# FE_Channel.net
KiCad netlist of a schematic drawn in Altium Designer
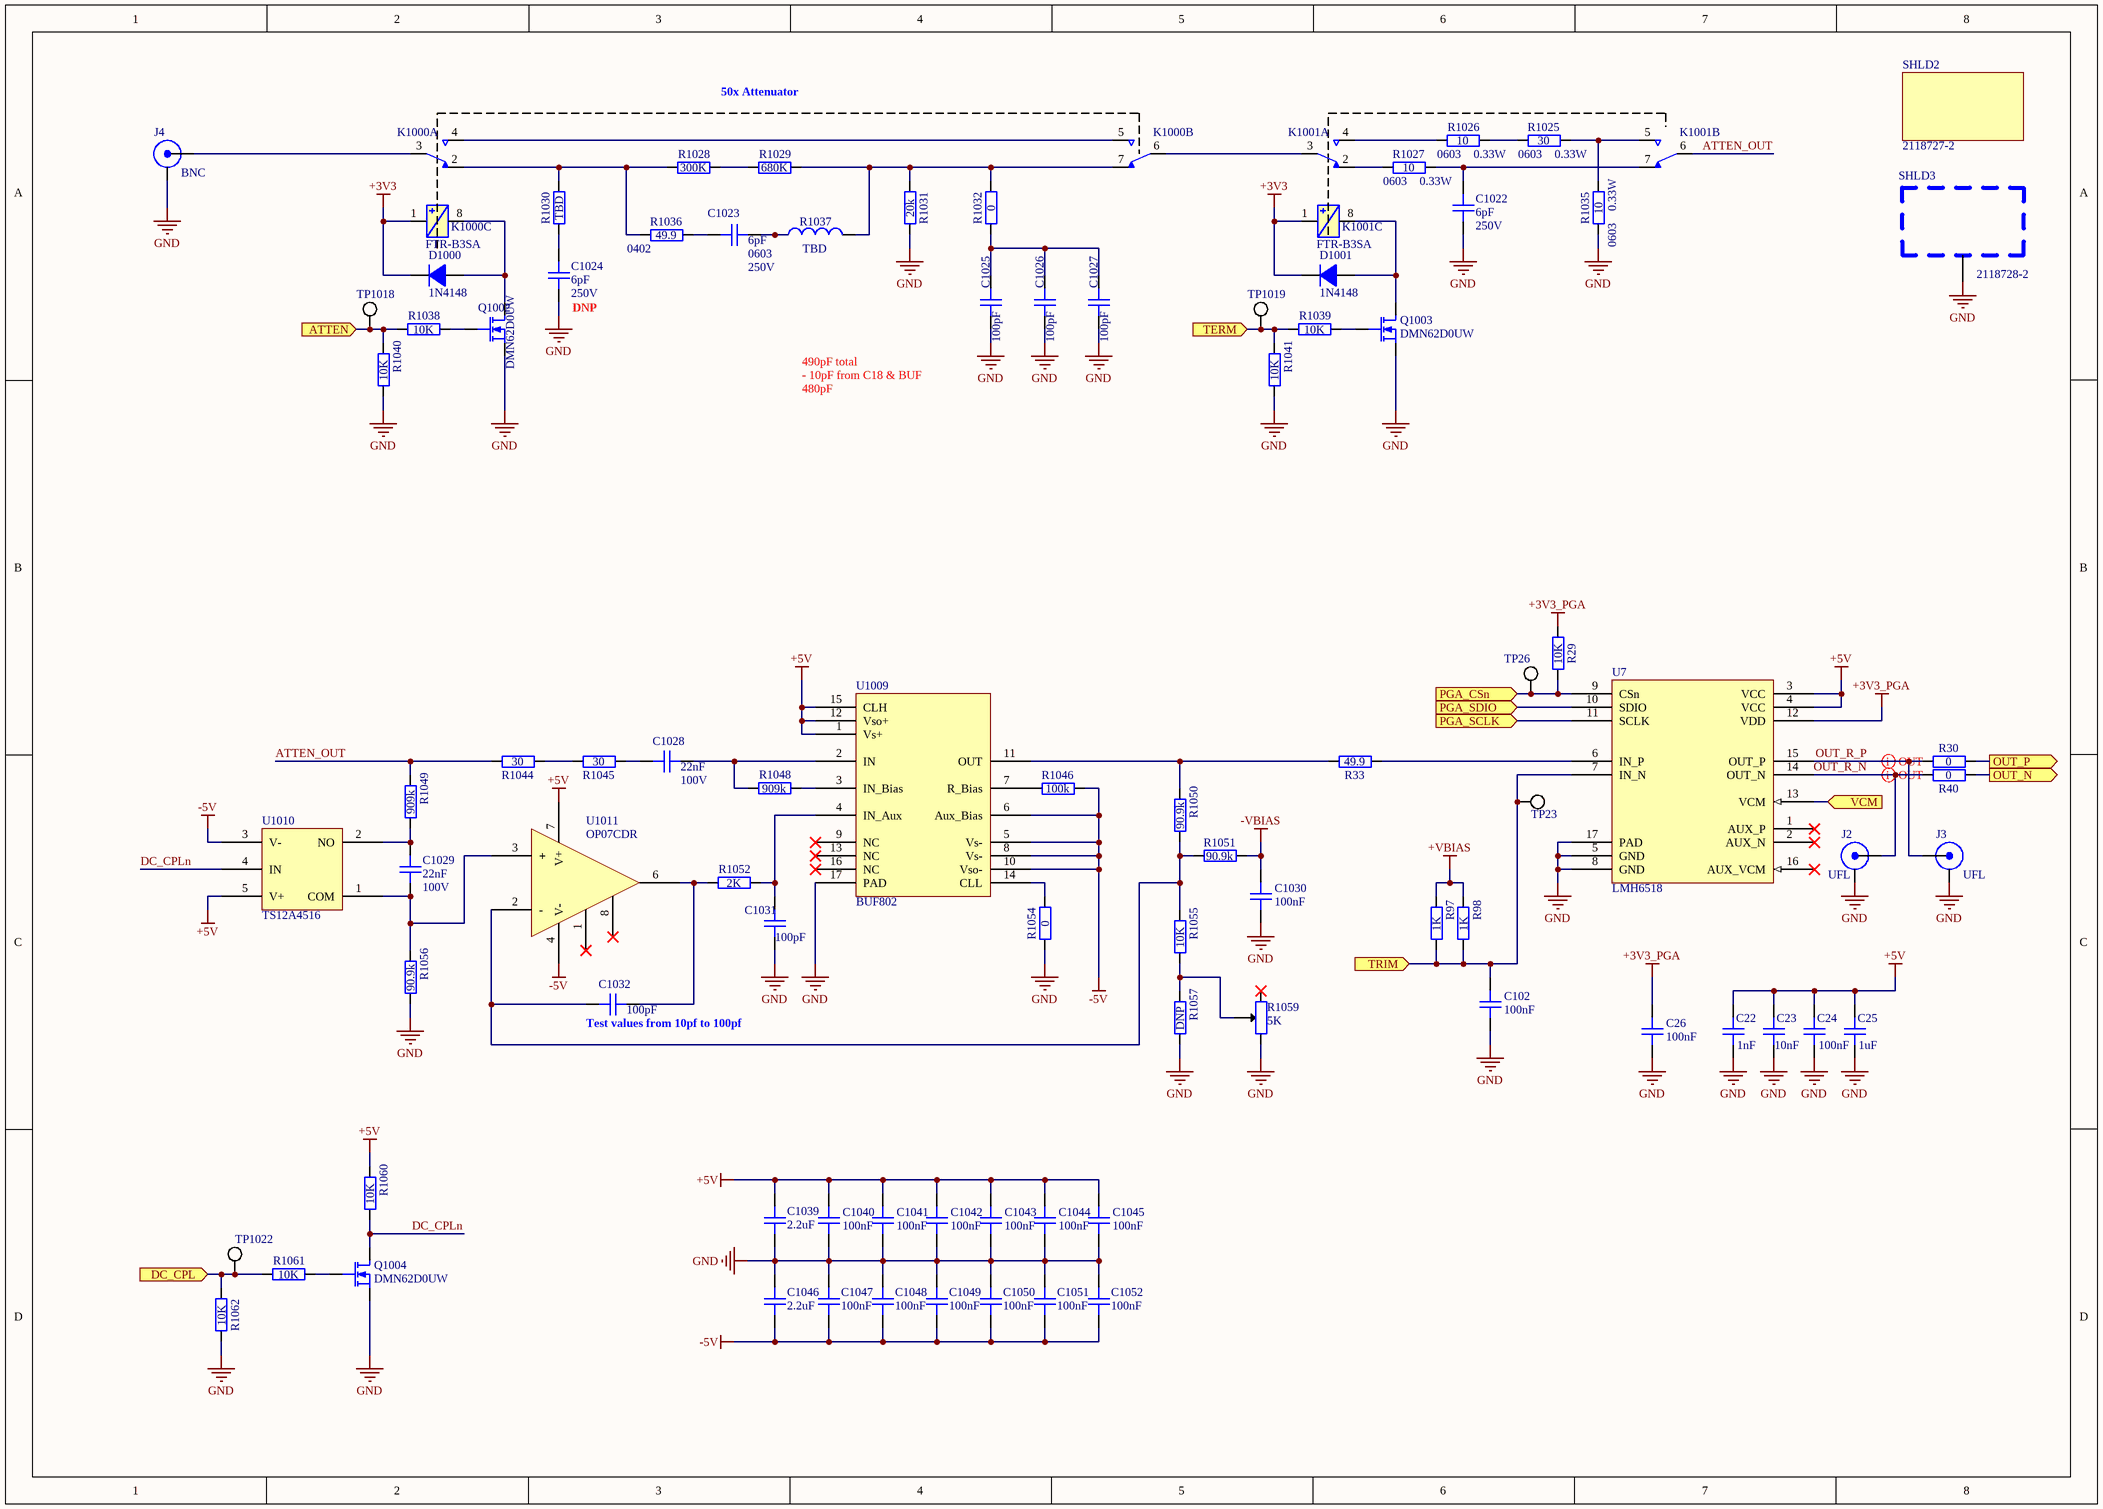
[diagram p0: FE_Channel.SchDoc]

(export (version "E")
  (design (tool "Eeschema 10.0.6"))
  (components
    (comp (ref "C22")
      (value "1nF")
      (footprint "GEN_C_0402")
      (libsource (lib "DSO") (part "CAP 1nF 50V C0G 0402"))
    )
    (comp (ref "C23")
      (value "10nF")
      (footprint "GEN_C_0402")
      (libsource (lib "DSO") (part "CAP 10nF 50V X7R 0402"))
    )
    (comp (ref "C24")
      (value "100nF")
      (footprint "GEN_C_0402")
      (libsource (lib "DSO") (part "CAP 100nF 16V X7R 0402"))
    )
    (comp (ref "C25")
      (value "1uF")
      (footprint "GEN_C_0402")
      (libsource (lib "DSO") (part "CAP 1uF 25V X5R 0402"))
    )
    (comp (ref "C26")
      (value "100nF")
      (footprint "GEN_C_0402")
      (libsource (lib "DSO") (part "CAP 100nF 16V X7R 0402"))
    )
    (comp (ref "C102")
      (value "100nF")
      (footprint "GEN_C_0402")
      (libsource (lib "DSO") (part "CAP 100nF 16V X7R 0402"))
    )
    (comp (ref "C1022")
      (value "6pF")
      (footprint "GEN_C_0603")
      (fields
        (field (name "MANUFACTURER") "KEMET")
        (field (name "MANUFACTURER PART NUMBER") "CBR06C609BAGAC")
        (field (name "VOLTAGE RATING") "250V")
      )
      (libsource (lib "DSO") (part "CAP 6pF 250V C0G 0603"))
    )
    (comp (ref "C1023")
      (value "6pF")
      (footprint "GEN_C_0603")
      (fields
        (field (name "PACKAGE") "0603")
        (field (name "VOLTAGE RATING") "250V")
        (field (name "MANUFACTURER") "KEMET")
        (field (name "MANUFACTURER PART NUMBER") "CBR06C609BAGAC")
      )
      (libsource (lib "DSO") (part "CAP 6pF 250V C0G 0603"))
    )
    (comp (ref "C1024")
      (value "6pF")
      (footprint "GEN_C_0603")
      (fields
        (field (name "MANUFACTURER") "KEMET")
        (field (name "MANUFACTURER PART NUMBER") "CBR06C609BAGAC")
        (field (name "VOLTAGE RATING") "250V")
      )
      (libsource (lib "DSO") (part "CAP 6pF 250V C0G 0603"))
    )
    (comp (ref "C1025")
      (value "100pF")
      (footprint "GEN_C_0402")
      (fields
        (field (name "MANUFACTURER") "Murata")
        (field (name "MANUFACTURER PART NUMBER") "GCM1555C1H101FA16D")
      )
      (libsource (lib "DSO") (part "CAP 100pF 50V C0G 0402"))
    )
    (comp (ref "C1026")
      (value "100pF")
      (footprint "GEN_C_0402")
      (fields
        (field (name "MANUFACTURER") "Murata")
        (field (name "MANUFACTURER PART NUMBER") "GCM1555C1H101FA16D")
      )
      (libsource (lib "DSO") (part "CAP 100pF 50V C0G 0402"))
    )
    (comp (ref "C1027")
      (value "100pF")
      (footprint "GEN_C_0402")
      (fields
        (field (name "MANUFACTURER") "Murata")
        (field (name "MANUFACTURER PART NUMBER") "GCM1555C1H101FA16D")
      )
      (libsource (lib "DSO") (part "CAP 100pF 50V C0G 0402"))
    )
    (comp (ref "C1028")
      (value "22nF")
      (footprint "GEN_C_0603")
      (fields (field (name "VOLTAGE RATING") "100V"))
      (libsource (lib "DSO") (part "CAP 22nF 100V X7R 0603"))
    )
    (comp (ref "C1029")
      (value "22nF")
      (footprint "GEN_C_0603")
      (fields (field (name "VOLTAGE RATING") "100V"))
      (libsource (lib "DSO") (part "CAP 22nF 100V X7R 0603"))
    )
    (comp (ref "C1030")
      (value "100nF")
      (footprint "GEN_C_0402")
      (libsource (lib "DSO") (part "CAP 100nF 16V X7R 0402"))
    )
    (comp (ref "C1031")
      (value "100pF")
      (footprint "GEN_C_0402")
      (libsource (lib "DSO") (part "CAP 100pF 50V C0G 0402"))
    )
    (comp (ref "C1032")
      (value "100pF")
      (footprint "GEN_C_0402")
      (libsource (lib "DSO") (part "CAP 100pF 50V C0G 0402"))
    )
    (comp (ref "C1039")
      (value "2.2uF")
      (footprint "GEN_C_0402")
      (libsource (lib "DSO") (part "CAP 2.2uF 10V X5R 0402"))
    )
    (comp (ref "C1040")
      (value "100nF")
      (footprint "GEN_C_0402")
      (libsource (lib "DSO") (part "CAP 100nF 16V X7R 0402"))
    )
    (comp (ref "C1041")
      (value "100nF")
      (footprint "GEN_C_0402")
      (libsource (lib "DSO") (part "CAP 100nF 16V X7R 0402"))
    )
    (comp (ref "C1042")
      (value "100nF")
      (footprint "GEN_C_0402")
      (libsource (lib "DSO") (part "CAP 100nF 16V X7R 0402"))
    )
    (comp (ref "C1043")
      (value "100nF")
      (footprint "GEN_C_0402")
      (libsource (lib "DSO") (part "CAP 100nF 16V X7R 0402"))
    )
    (comp (ref "C1044")
      (value "100nF")
      (footprint "GEN_C_0402")
      (libsource (lib "DSO") (part "CAP 100nF 16V X7R 0402"))
    )
    (comp (ref "C1045")
      (value "100nF")
      (footprint "GEN_C_0402")
      (libsource (lib "DSO") (part "CAP 100nF 16V X7R 0402"))
    )
    (comp (ref "C1046")
      (value "2.2uF")
      (footprint "GEN_C_0402")
      (libsource (lib "DSO") (part "CAP 2.2uF 10V X5R 0402"))
    )
    (comp (ref "C1047")
      (value "100nF")
      (footprint "GEN_C_0402")
      (libsource (lib "DSO") (part "CAP 100nF 16V X7R 0402"))
    )
    (comp (ref "C1048")
      (value "100nF")
      (footprint "GEN_C_0402")
      (libsource (lib "DSO") (part "CAP 100nF 16V X7R 0402"))
    )
    (comp (ref "C1049")
      (value "100nF")
      (footprint "GEN_C_0402")
      (libsource (lib "DSO") (part "CAP 100nF 16V X7R 0402"))
    )
    (comp (ref "C1050")
      (value "100nF")
      (footprint "GEN_C_0402")
      (libsource (lib "DSO") (part "CAP 100nF 16V X7R 0402"))
    )
    (comp (ref "C1051")
      (value "100nF")
      (footprint "GEN_C_0402")
      (libsource (lib "DSO") (part "CAP 100nF 16V X7R 0402"))
    )
    (comp (ref "C1052")
      (value "100nF")
      (footprint "GEN_C_0402")
      (libsource (lib "DSO") (part "CAP 100nF 16V X7R 0402"))
    )
    (comp (ref "D1000")
      (value "1N4148")
      (footprint "GEN_SOD_323")
      (libsource (lib "DSO") (part "DIODE 1N4148"))
    )
    (comp (ref "D1001")
      (value "1N4148")
      (footprint "GEN_SOD_323")
      (libsource (lib "DSO") (part "DIODE 1N4148"))
    )
    (comp (ref "J2") (value "UFL") (footprint "TE_2334884-1") (libsource (lib "DSO") (part "UFL Jack SMD")))
    (comp (ref "J3") (value "UFL") (footprint "TE_2334884-1") (libsource (lib "DSO") (part "UFL Jack SMD")))
    (comp (ref "J4") (value "BNC") (footprint "MOL_0731000105") (libsource (lib "DSO") (part "BNC JACK R/A")))
    (comp (ref "K1000")
      (value "FTR-B3SA")
      (footprint "FUJ_FTR-B3SA")
      (libsource (lib "DSO") (part "RELAY DPDT-NO FTR-B3SA"))
    )
    (comp (ref "K1001")
      (value "FTR-B3SA")
      (footprint "FUJ_FTR-B3SA")
      (libsource (lib "DSO") (part "RELAY DPDT-NO FTR-B3SA"))
    )
    (comp (ref "Q1002")
      (value "DMN62D0UW")
      (footprint "GEN_SOT_323")
      (libsource (lib "DSO") (part "NMOS DMN62D0UW"))
    )
    (comp (ref "Q1003")
      (value "DMN62D0UW")
      (footprint "GEN_SOT_323")
      (libsource (lib "DSO") (part "NMOS DMN62D0UW"))
    )
    (comp (ref "Q1004")
      (value "DMN62D0UW")
      (footprint "GEN_SOT_323")
      (libsource (lib "DSO") (part "NMOS DMN62D0UW"))
    )
    (comp (ref "R29")
      (value "10K")
      (footprint "GEN_R_0402")
      (fields (field (name "TOLERANCE") "1%"))
      (libsource (lib "DSO") (part "RES 10K OHM 1% 1/10W 0402"))
    )
    (comp (ref "R30")
      (value "0")
      (footprint "GEN_R_0402")
      (libsource (lib "") (part "RES 0 OHM 1/16W 0402_1"))
    )
    (comp (ref "R33")
      (value "49.9")
      (footprint "GEN_R_0402")
      (fields
        (field (name "TOLERANCE") "1%")
        (field (name "MANUFACTURER") "Yageo")
        (field (name "MANUFACTURER PART NUMBER") "RC0402FR-0749R9L")
      )
      (libsource (lib "DSO") (part "RES 49.9 OHM 1% 1/10W 0402"))
    )
    (comp (ref "R40")
      (value "0")
      (footprint "GEN_R_0402")
      (libsource (lib "") (part "RES 0 OHM 1/16W 0402_1"))
    )
    (comp (ref "R97")
      (value "1K")
      (footprint "GEN_R_0402")
      (fields (field (name "TOLERANCE") "1%"))
      (libsource (lib "") (part "RES 1K OHM 1% 1/10W 0402_1"))
    )
    (comp (ref "R98")
      (value "1K")
      (footprint "GEN_R_0402")
      (fields (field (name "TOLERANCE") "1%"))
      (libsource (lib "DSO") (part "RES 1K OHM 1% 1/10W 0402"))
    )
    (comp (ref "R1025")
      (value "30")
      (footprint "GEN_R_0603")
      (fields
        (field (name "TOLERANCE") "1%")
        (field (name "POWER RATING") "0.33W")
        (field (name "PACKAGE") "0603")
      )
      (libsource (lib "DSO") (part "RES 30 OHM 1% 1/3W 0603"))
    )
    (comp (ref "R1026")
      (value "10")
      (footprint "GEN_R_0603")
      (fields
        (field (name "PACKAGE") "0603")
        (field (name "TOLERANCE") "1%")
        (field (name "POWER RATING") "0.33W")
      )
      (libsource (lib "") (part "RES 10 OHM 1% 1/3W 0603_1"))
    )
    (comp (ref "R1027")
      (value "10")
      (footprint "GEN_R_0603")
      (fields
        (field (name "TOLERANCE") "1%")
        (field (name "PACKAGE") "0603")
        (field (name "MANUFACTURER") "KOA Speer")
        (field (name "MANUFACTURER PART NUMBER") "SG73P1JTTD10R0F")
        (field (name "POWER RATING") "0.33W")
      )
      (libsource (lib "") (part "RES 10 OHM 1% 1/3W 0603_1"))
    )
    (comp (ref "R1028")
      (value "300K")
      (footprint "GEN_R_0402")
      (fields
        (field (name "TOLERANCE") "1%")
        (field (name "MANUFACTURER") "Panasonic")
        (field (name "MANUFACTURER PART NUMBER") "ERJ-2RKF3003X")
      )
      (libsource (lib "DSO") (part "RES 300K OHM 1% 1/10W 0402"))
    )
    (comp (ref "R1029")
      (value "680K")
      (footprint "GEN_R_0402")
      (fields
        (field (name "TOLERANCE") "1%")
        (field (name "MANUFACTURER") "Yageo")
        (field (name "MANUFACTURER PART NUMBER") "RC0402FR-07681KL")
      )
      (libsource (lib "DSO") (part "RES 680K OHM 1% 1/16W 0402"))
    )
    (comp (ref "R1030")
      (value "TBD")
      (footprint "GEN_R_0402")
      (fields (field (name "TOLERANCE") "1%"))
      (libsource (lib "DSO") (part "RES TBD 0402"))
    )
    (comp (ref "R1031")
      (value "20k")
      (footprint "GEN_R_0402")
      (fields
        (field (name "TOLERANCE") "1%")
        (field (name "MANUFACTURER") "Yageo")
        (field (name "MANUFACTURER PART NUMBER") "RC0402FR-0720KL")
      )
      (libsource (lib "DSO") (part "RES 20K OHM 1% 1/16W 0402"))
    )
    (comp (ref "R1032")
      (value "0")
      (footprint "GEN_R_0402")
      (fields
        (field (name "MANUFACTURER") "Yageo")
        (field (name "MANUFACTURER PART NUMBER") "RC0402JR-070RL")
      )
      (libsource (lib "DSO") (part "RES 0 OHM 1/16W 0402"))
    )
    (comp (ref "R1035")
      (value "10")
      (footprint "GEN_R_0603")
      (fields
        (field (name "TOLERANCE") "1%")
        (field (name "POWER RATING") "0.33W")
        (field (name "PACKAGE") "0603")
      )
      (libsource (lib "DSO") (part "RES 10 OHM 1% 1/3W 0603"))
    )
    (comp (ref "R1036")
      (value "49.9")
      (footprint "GEN_R_0402")
      (fields
        (field (name "TOLERANCE") "1%")
        (field (name "PACKAGE") "0402")
        (field (name "MANUFACTURER") "Yageo")
        (field (name "MANUFACTURER PART NUMBER") "RC0402FR-0749R9L")
      )
      (libsource (lib "DSO") (part "RES 49.9 OHM 1% 1/10W 0402"))
    )
    (comp (ref "R1037") (value "TBD") (footprint "GEN_L_0402") (libsource (lib "DSO") (part "IND TBD 0402")))
    (comp (ref "R1038")
      (value "10K")
      (footprint "GEN_R_0402")
      (fields (field (name "TOLERANCE") "1%"))
      (libsource (lib "") (part "RES 10K OHM 1% 1/10W 0402_2"))
    )
    (comp (ref "R1039")
      (value "10K")
      (footprint "GEN_R_0402")
      (fields (field (name "TOLERANCE") "1%"))
      (libsource (lib "") (part "RES 10K OHM 1% 1/10W 0402_2"))
    )
    (comp (ref "R1040")
      (value "10K")
      (footprint "GEN_R_0402")
      (fields (field (name "TOLERANCE") "1%"))
      (libsource (lib "DSO") (part "RES 10K OHM 1% 1/10W 0402"))
    )
    (comp (ref "R1041")
      (value "10K")
      (footprint "GEN_R_0402")
      (fields (field (name "TOLERANCE") "1%"))
      (libsource (lib "DSO") (part "RES 10K OHM 1% 1/10W 0402"))
    )
    (comp (ref "R1044")
      (value "30")
      (footprint "GEN_R_0603")
      (fields
        (field (name "TOLERANCE") "1%")
        (field (name "MANUFACTURER") "KOA Speer")
        (field (name "MANUFACTURER PART NUMBER") "SG73P1JTTD30R0F")
      )
      (libsource (lib "DSO") (part "RES 30 OHM 1% 1/3W 0603"))
    )
    (comp (ref "R1045")
      (value "30")
      (footprint "GEN_R_0603")
      (fields
        (field (name "TOLERANCE") "1%")
        (field (name "MANUFACTURER") "KOA Speer")
        (field (name "MANUFACTURER PART NUMBER") "SG73P1JTTD30R0F")
      )
      (libsource (lib "DSO") (part "RES 30 OHM 1% 1/3W 0603"))
    )
    (comp (ref "R1046")
      (value "100k")
      (footprint "GEN_R_0402")
      (fields (field (name "TOLERANCE") "1%"))
      (libsource (lib "DSO") (part "RES 100K OHM 1% 1/10W 0402"))
    )
    (comp (ref "R1048")
      (value "909k")
      (footprint "GEN_R_0402")
      (fields (field (name "TOLERANCE") "1%"))
      (libsource (lib "") (part "RES 909K OHM 1% 1/16W 0402_1"))
    )
    (comp (ref "R1049")
      (value "909k")
      (footprint "GEN_R_0402")
      (fields (field (name "TOLERANCE") "1%"))
      (libsource (lib "DSO") (part "RES 909K OHM 1% 1/16W 0402"))
    )
    (comp (ref "R1050")
      (value "90.9k")
      (footprint "GEN_R_0402")
      (fields (field (name "TOLERANCE") "1%"))
      (libsource (lib "DSO") (part "RES 90.9K OHM 1% 1/16W 0402"))
    )
    (comp (ref "R1051")
      (value "90.9k")
      (footprint "GEN_R_0402")
      (fields (field (name "TOLERANCE") "1%"))
      (libsource (lib "") (part "RES 90.9K OHM 1% 1/16W 0402_1"))
    )
    (comp (ref "R1052")
      (value "2K")
      (footprint "GEN_R_0402")
      (fields (field (name "TOLERANCE") "1%"))
      (libsource (lib "DSO") (part "RES 2K OHM 1% 1/16W 0402"))
    )
    (comp (ref "R1054")
      (value "0")
      (footprint "GEN_R_0402")
      (libsource (lib "DSO") (part "RES 0 OHM 1/16W 0402"))
    )
    (comp (ref "R1055")
      (value "10K")
      (footprint "GEN_R_0402")
      (fields (field (name "TOLERANCE") "1%"))
      (libsource (lib "DSO") (part "RES 10K OHM 1% 1/10W 0402"))
    )
    (comp (ref "R1056")
      (value "90.9k")
      (footprint "GEN_R_0402")
      (fields (field (name "TOLERANCE") "1%"))
      (libsource (lib "DSO") (part "RES 90.9K OHM 1% 1/16W 0402"))
    )
    (comp (ref "R1057")
      (value "DNP")
      (footprint "GEN_R_0402")
      (fields (field (name "TOLERANCE") "1%"))
      (libsource (lib "DSO") (part "RES DNP 0402"))
    )
    (comp (ref "R1059")
      (value "5K")
      (footprint "BOU_3mm_POT")
      (fields (field (name "TOLERANCE") "1%"))
      (libsource (lib "DSO") (part "TRIMMER 5K OHM 0.1W J LEAD TOP"))
    )
    (comp (ref "R1060")
      (value "10K")
      (footprint "GEN_R_0402")
      (fields
        (field (name "TOLERANCE") "1%")
        (field (name "MANUFACTURER") "Panasonic")
        (field (name "MANUFACTURER PART NUMBER") "ERJ-2RKF1002X")
      )
      (libsource (lib "DSO") (part "RES 10K OHM 1% 1/10W 0402"))
    )
    (comp (ref "R1061")
      (value "10K")
      (footprint "GEN_R_0402")
      (fields (field (name "TOLERANCE") "1%"))
      (libsource (lib "") (part "RES 10K OHM 1% 1/10W 0402_2"))
    )
    (comp (ref "R1062")
      (value "10K")
      (footprint "GEN_R_0402")
      (fields
        (field (name "TOLERANCE") "1%")
        (field (name "MANUFACTURER") "Panasonic")
        (field (name "MANUFACTURER PART NUMBER") "ERJ-2RKF1002X")
      )
      (libsource (lib "") (part "RES 10K OHM 1% 1/10W 0402_1"))
    )
    (comp (ref "SHLD2") (value "2118727-2") (libsource (lib "DSO") (part "SHIELD 2118727-2")))
    (comp (ref "SHLD3")
      (value "2118728-2")
      (footprint "TE_2118728-2")
      (libsource (lib "DSO") (part "SHIELD 2118728-2"))
    )
    (comp (ref "TP23") (value "PCB") (footprint "GEN_TP_PCB") (libsource (lib "DSO") (part "TP PCB 1mm")))
    (comp (ref "TP26") (value "PCB") (footprint "GEN_TP_PCB") (libsource (lib "DSO") (part "TP PCB 1mm")))
    (comp (ref "TP1018") (value "PCB") (footprint "GEN_TP_PCB") (libsource (lib "DSO") (part "TP PCB 1mm")))
    (comp (ref "TP1019") (value "PCB") (footprint "GEN_TP_PCB") (libsource (lib "DSO") (part "TP PCB 1mm")))
    (comp (ref "TP1022") (value "PCB") (footprint "GEN_TP_PCB") (libsource (lib "DSO") (part "TP PCB 1mm")))
    (comp (ref "U7")
      (value "LMH6518")
      (footprint "TI_WQFN_RGH0016A")
      (libsource (lib "DSO") (part "IC PGA LMH6518"))
    )
    (comp (ref "U1009")
      (value "BUF802")
      (footprint "TI_VQFN_RGT0016C")
      (libsource (lib "DSO") (part "IC BUFFER AMP BUF802"))
    )
    (comp (ref "U1010")
      (value "TS12A4516")
      (footprint "GEN_SOT23_5_950_2900X1600X1450")
      (fields
        (field (name "MANUFACTURER") "Texas Instruments")
        (field (name "MANUFACTURER PART NUMBER") "TS12A4516DBVR")
      )
      (libsource (lib "DSO") (part "IC SWITCH SPST TS12A4516DBVR"))
    )
    (comp (ref "U1011")
      (value "OP07CDR")
      (footprint "TI_SOIC8_D0008A")
      (libsource (lib "DSO") (part "IC OPAMP OP07CDR"))
    )
  )
  (nets
    (net (code "1") (name "+3V3") (class "Default")
      (node (ref "D1000") (pin "1") (pinfunction "K_1") (pintype "passive"))
      (node (ref "D1001") (pin "1") (pinfunction "K_1") (pintype "passive"))
      (node (ref "K1000") (pin "1") (pinfunction "1_1") (pintype "passive"))
      (node (ref "K1001") (pin "1") (pinfunction "1_1") (pintype "passive"))
    )
    (net (code "2") (name "+3V3_PGA") (class "Default")
      (node (ref "C26") (pin "2") (pinfunction "2_2") (pintype "passive"))
      (node (ref "R29") (pin "2") (pinfunction "2_2") (pintype "passive"))
      (node (ref "U7") (pin "12") (pinfunction "VDD_12") (pintype "power_in"))
    )
    (net (code "3") (name "+5V") (class "Default")
      (node (ref "C1039") (pin "2") (pinfunction "2_2") (pintype "passive"))
      (node (ref "C1040") (pin "1") (pinfunction "1_1") (pintype "passive"))
      (node (ref "C1041") (pin "1") (pinfunction "1_1") (pintype "passive"))
      (node (ref "C1042") (pin "1") (pinfunction "1_1") (pintype "passive"))
      (node (ref "C1043") (pin "2") (pinfunction "2_2") (pintype "passive"))
      (node (ref "C1044") (pin "2") (pinfunction "2_2") (pintype "passive"))
      (node (ref "C1045") (pin "2") (pinfunction "2_2") (pintype "passive"))
      (node (ref "C22") (pin "2") (pinfunction "2_2") (pintype "passive"))
      (node (ref "C23") (pin "2") (pinfunction "2_2") (pintype "passive"))
      (node (ref "C24") (pin "2") (pinfunction "2_2") (pintype "passive"))
      (node (ref "C25") (pin "2") (pinfunction "2_2") (pintype "passive"))
      (node (ref "R1060") (pin "2") (pinfunction "2_2") (pintype "passive"))
      (node (ref "U1009") (pin "1") (pinfunction "Vs+_1") (pintype "passive"))
      (node (ref "U1009") (pin "12") (pinfunction "Vso+_12") (pintype "passive"))
      (node (ref "U1009") (pin "15") (pinfunction "CLH_15") (pintype "passive"))
      (node (ref "U1010") (pin "5") (pinfunction "V+_5") (pintype "passive"))
      (node (ref "U1011") (pin "7") (pinfunction "V+_7") (pintype "passive"))
      (node (ref "U7") (pin "3") (pinfunction "VCC_3") (pintype "power_in"))
      (node (ref "U7") (pin "4") (pinfunction "VCC_4") (pintype "power_in"))
    )
    (net (code "4") (name "+VBIAS") (class "Default")
      (node (ref "R97") (pin "2") (pinfunction "2_2") (pintype "passive"))
      (node (ref "R98") (pin "1") (pinfunction "1_1") (pintype "passive"))
    )
    (net (code "5") (name "-5V") (class "Default")
      (node (ref "C1046") (pin "2") (pinfunction "2_2") (pintype "passive"))
      (node (ref "C1047") (pin "2") (pinfunction "2_2") (pintype "passive"))
      (node (ref "C1048") (pin "1") (pinfunction "1_1") (pintype "passive"))
      (node (ref "C1049") (pin "1") (pinfunction "1_1") (pintype "passive"))
      (node (ref "C1050") (pin "1") (pinfunction "1_1") (pintype "passive"))
      (node (ref "C1051") (pin "2") (pinfunction "2_2") (pintype "passive"))
      (node (ref "C1052") (pin "2") (pinfunction "2_2") (pintype "passive"))
      (node (ref "R1046") (pin "2") (pinfunction "2_2") (pintype "passive"))
      (node (ref "U1009") (pin "10") (pinfunction "Vso-_10") (pintype "passive"))
      (node (ref "U1009") (pin "5") (pinfunction "Vs-_5") (pintype "passive"))
      (node (ref "U1009") (pin "6") (pinfunction "Aux_Bias_6") (pintype "passive"))
      (node (ref "U1009") (pin "8") (pinfunction "Vs-_8") (pintype "passive"))
      (node (ref "U1010") (pin "3") (pinfunction "V-_3") (pintype "passive"))
      (node (ref "U1011") (pin "4") (pinfunction "V-_4") (pintype "passive"))
    )
    (net (code "6") (name "-VBIAS") (class "Default")
      (node (ref "C1030") (pin "1") (pinfunction "1_1") (pintype "passive"))
      (node (ref "R1051") (pin "1") (pinfunction "1_1") (pintype "passive"))
    )
    (net (code "7") (name "/ATTEN") (class "Default")
      (node (ref "R1038") (pin "2") (pinfunction "2_2") (pintype "passive"))
      (node (ref "R1040") (pin "2") (pinfunction "2_2") (pintype "passive"))
      (node (ref "TP1018") (pin "1") (pinfunction "1_1") (pintype "passive"))
    )
    (net (code "8") (name "/ATTEN_OUT") (class "Default")
      (node (ref "K1001") (pin "6") (pinfunction "6_6") (pintype "passive"))
      (node (ref "R1044") (pin "1") (pinfunction "1_1") (pintype "passive"))
      (node (ref "R1049") (pin "2") (pinfunction "2_2") (pintype "passive"))
    )
    (net (code "9") (name "/DC_CPL") (class "Default")
      (node (ref "R1061") (pin "2") (pinfunction "2_2") (pintype "passive"))
      (node (ref "R1062") (pin "2") (pinfunction "2_2") (pintype "passive"))
      (node (ref "TP1022") (pin "1") (pinfunction "1_1") (pintype "passive"))
    )
    (net (code "10") (name "/DC_CPLn") (class "Default")
      (node (ref "Q1004") (pin "1") (pinfunction "D_1") (pintype "passive"))
      (node (ref "R1060") (pin "1") (pinfunction "1_1") (pintype "passive"))
      (node (ref "U1010") (pin "4") (pinfunction "IN_4") (pintype "passive"))
    )
    (net (code "11") (name "/OUT_N") (class "Default")
      (node (ref "R40") (pin "2") (pinfunction "2_2") (pintype "passive"))
    )
    (net (code "12") (name "/OUT_P") (class "Default")
      (node (ref "R30") (pin "2") (pinfunction "2_2") (pintype "passive"))
    )
    (net (code "13") (name "/OUT_R_N") (class "Default")
      (node (ref "J2") (pin "1") (pinfunction "Signal_1") (pintype "passive"))
      (node (ref "R40") (pin "1") (pinfunction "1_1") (pintype "passive"))
      (node (ref "U7") (pin "14") (pinfunction "OUT_N_14") (pintype "passive"))
    )
    (net (code "14") (name "/OUT_R_P") (class "Default")
      (node (ref "J3") (pin "1") (pinfunction "Signal_1") (pintype "passive"))
      (node (ref "R30") (pin "1") (pinfunction "1_1") (pintype "passive"))
      (node (ref "U7") (pin "15") (pinfunction "OUT_P_15") (pintype "passive"))
    )
    (net (code "15") (name "/PGA_CSn") (class "Default")
      (node (ref "R29") (pin "1") (pinfunction "1_1") (pintype "passive"))
      (node (ref "TP26") (pin "1") (pinfunction "1_1") (pintype "passive"))
      (node (ref "U7") (pin "9") (pinfunction "CSn_9") (pintype "passive"))
    )
    (net (code "16") (name "/PGA_SCLK") (class "Default")
      (node (ref "U7") (pin "11") (pinfunction "SCLK_11") (pintype "passive"))
    )
    (net (code "17") (name "/PGA_SDIO") (class "Default")
      (node (ref "U7") (pin "10") (pinfunction "SDIO_10") (pintype "passive"))
    )
    (net (code "18") (name "/TERM") (class "Default")
      (node (ref "R1039") (pin "2") (pinfunction "2_2") (pintype "passive"))
      (node (ref "R1041") (pin "2") (pinfunction "2_2") (pintype "passive"))
      (node (ref "TP1019") (pin "1") (pinfunction "1_1") (pintype "passive"))
    )
    (net (code "19") (name "/TRIM") (class "Default")
      (node (ref "C102") (pin "1") (pinfunction "1_1") (pintype "passive"))
      (node (ref "R97") (pin "1") (pinfunction "1_1") (pintype "passive"))
      (node (ref "R98") (pin "2") (pinfunction "2_2") (pintype "passive"))
      (node (ref "TP23") (pin "1") (pinfunction "1_1") (pintype "passive"))
      (node (ref "U7") (pin "7") (pinfunction "IN_N_7") (pintype "passive"))
    )
    (net (code "20") (name "/VCM") (class "Default")
      (node (ref "U7") (pin "13") (pinfunction "VCM_13") (pintype "input"))
    )
    (net (code "21") (name "GND") (class "Default")
      (node (ref "C102") (pin "2") (pinfunction "2_2") (pintype "passive"))
      (node (ref "C1022") (pin "2") (pinfunction "2_2") (pintype "passive"))
      (node (ref "C1024") (pin "1") (pinfunction "1_1") (pintype "passive"))
      (node (ref "C1025") (pin "1") (pinfunction "1_1") (pintype "passive"))
      (node (ref "C1026") (pin "1") (pinfunction "1_1") (pintype "passive"))
      (node (ref "C1027") (pin "1") (pinfunction "1_1") (pintype "passive"))
      (node (ref "C1030") (pin "2") (pinfunction "2_2") (pintype "passive"))
      (node (ref "C1031") (pin "1") (pinfunction "1_1") (pintype "passive"))
      (node (ref "C1039") (pin "1") (pinfunction "1_1") (pintype "passive"))
      (node (ref "C1040") (pin "2") (pinfunction "2_2") (pintype "passive"))
      (node (ref "C1041") (pin "2") (pinfunction "2_2") (pintype "passive"))
      (node (ref "C1042") (pin "2") (pinfunction "2_2") (pintype "passive"))
      (node (ref "C1043") (pin "1") (pinfunction "1_1") (pintype "passive"))
      (node (ref "C1044") (pin "1") (pinfunction "1_1") (pintype "passive"))
      (node (ref "C1045") (pin "1") (pinfunction "1_1") (pintype "passive"))
      (node (ref "C1046") (pin "1") (pinfunction "1_1") (pintype "passive"))
      (node (ref "C1047") (pin "1") (pinfunction "1_1") (pintype "passive"))
      (node (ref "C1048") (pin "2") (pinfunction "2_2") (pintype "passive"))
      (node (ref "C1049") (pin "2") (pinfunction "2_2") (pintype "passive"))
      (node (ref "C1050") (pin "2") (pinfunction "2_2") (pintype "passive"))
      (node (ref "C1051") (pin "1") (pinfunction "1_1") (pintype "passive"))
      (node (ref "C1052") (pin "1") (pinfunction "1_1") (pintype "passive"))
      (node (ref "C22") (pin "1") (pinfunction "1_1") (pintype "passive"))
      (node (ref "C23") (pin "1") (pinfunction "1_1") (pintype "passive"))
      (node (ref "C24") (pin "1") (pinfunction "1_1") (pintype "passive"))
      (node (ref "C25") (pin "1") (pinfunction "1_1") (pintype "passive"))
      (node (ref "C26") (pin "1") (pinfunction "1_1") (pintype "passive"))
      (node (ref "J2") (pin "2") (pinfunction "SHIELD_2") (pintype "passive"))
      (node (ref "J3") (pin "2") (pinfunction "SHIELD_2") (pintype "passive"))
      (node (ref "J4") (pin "2") (pinfunction "SHIELD_2") (pintype "passive"))
      (node (ref "Q1002") (pin "3") (pinfunction "S_3") (pintype "passive"))
      (node (ref "Q1003") (pin "3") (pinfunction "S_3") (pintype "passive"))
      (node (ref "Q1004") (pin "3") (pinfunction "S_3") (pintype "passive"))
      (node (ref "R1031") (pin "1") (pinfunction "1_1") (pintype "passive"))
      (node (ref "R1035") (pin "1") (pinfunction "1_1") (pintype "passive"))
      (node (ref "R1040") (pin "1") (pinfunction "1_1") (pintype "passive"))
      (node (ref "R1041") (pin "1") (pinfunction "1_1") (pintype "passive"))
      (node (ref "R1054") (pin "1") (pinfunction "1_1") (pintype "passive"))
      (node (ref "R1056") (pin "1") (pinfunction "1_1") (pintype "passive"))
      (node (ref "R1057") (pin "1") (pinfunction "1_1") (pintype "passive"))
      (node (ref "R1059") (pin "3") (pinfunction "3_3") (pintype "passive"))
      (node (ref "R1062") (pin "1") (pinfunction "1_1") (pintype "passive"))
      (node (ref "SHLD3") (pin "1") (pinfunction "1_1") (pintype "passive"))
      (node (ref "U1009") (pin "17") (pinfunction "PAD_17") (pintype "passive"))
      (node (ref "U7") (pin "17") (pinfunction "PAD_17") (pintype "power_in"))
      (node (ref "U7") (pin "5") (pinfunction "GND_5") (pintype "power_in"))
      (node (ref "U7") (pin "8") (pinfunction "GND_8") (pintype "power_in"))
    )
    (net (code "22") (name "Net-(C1022-Pad1)") (class "Default")
      (node (ref "C1022") (pin "1") (pinfunction "1_1") (pintype "passive"))
      (node (ref "K1001") (pin "7") (pinfunction "7_7") (pintype "passive"))
      (node (ref "R1027") (pin "2") (pinfunction "2_2") (pintype "passive"))
    )
    (net (code "23") (name "Net-(C1023-Pad1)") (class "Default")
      (node (ref "C1023") (pin "1") (pinfunction "1_1") (pintype "passive"))
      (node (ref "R1037") (pin "1") (pinfunction "1_1") (pintype "passive"))
    )
    (net (code "24") (name "Net-(C1023-Pad2)") (class "Default")
      (node (ref "C1023") (pin "2") (pinfunction "2_2") (pintype "passive"))
      (node (ref "R1036") (pin "2") (pinfunction "2_2") (pintype "passive"))
    )
    (net (code "25") (name "Net-(C1024-Pad2)") (class "Default")
      (node (ref "C1024") (pin "2") (pinfunction "2_2") (pintype "passive"))
      (node (ref "R1030") (pin "1") (pinfunction "1_1") (pintype "passive"))
    )
    (net (code "26") (name "Net-(C1025-Pad2)") (class "Default")
      (node (ref "C1025") (pin "2") (pinfunction "2_2") (pintype "passive"))
      (node (ref "C1026") (pin "2") (pinfunction "2_2") (pintype "passive"))
      (node (ref "C1027") (pin "2") (pinfunction "2_2") (pintype "passive"))
      (node (ref "R1032") (pin "1") (pinfunction "1_1") (pintype "passive"))
    )
    (net (code "27") (name "Net-(C1028-Pad2)") (class "Default")
      (node (ref "C1028") (pin "2") (pinfunction "2_2") (pintype "passive"))
      (node (ref "R1045") (pin "2") (pinfunction "2_2") (pintype "passive"))
    )
    (net (code "28") (name "Net-(D1000-A)") (class "Default")
      (node (ref "D1000") (pin "2") (pinfunction "A_2") (pintype "passive"))
      (node (ref "K1000") (pin "8") (pinfunction "8_8") (pintype "passive"))
      (node (ref "Q1002") (pin "1") (pinfunction "D_1") (pintype "passive"))
    )
    (net (code "29") (name "Net-(D1001-A)") (class "Default")
      (node (ref "D1001") (pin "2") (pinfunction "A_2") (pintype "passive"))
      (node (ref "K1001") (pin "8") (pinfunction "8_8") (pintype "passive"))
      (node (ref "Q1003") (pin "1") (pinfunction "D_1") (pintype "passive"))
    )
    (net (code "30") (name "Net-(J4-Signal)") (class "Default")
      (node (ref "J4") (pin "1") (pinfunction "Signal_1") (pintype "passive"))
      (node (ref "K1000") (pin "3") (pinfunction "3_3") (pintype "passive"))
    )
    (net (code "31") (name "Net-(K1000-Pad2)") (class "Default")
      (node (ref "K1000") (pin "2") (pinfunction "2_2") (pintype "passive"))
      (node (ref "R1028") (pin "1") (pinfunction "1_1") (pintype "passive"))
      (node (ref "R1030") (pin "2") (pinfunction "2_2") (pintype "passive"))
      (node (ref "R1036") (pin "1") (pinfunction "1_1") (pintype "passive"))
    )
    (net (code "32") (name "Net-(K1000-Pad4)") (class "Default")
      (node (ref "K1000") (pin "4") (pinfunction "4_4") (pintype "passive"))
      (node (ref "K1000") (pin "5") (pinfunction "5_5") (pintype "passive"))
    )
    (net (code "33") (name "Net-(K1000-Pad6)") (class "Default")
      (node (ref "K1000") (pin "6") (pinfunction "6_6") (pintype "passive"))
      (node (ref "K1001") (pin "3") (pinfunction "3_3") (pintype "passive"))
    )
    (net (code "34") (name "Net-(K1000-Pad7)") (class "Default")
      (node (ref "K1000") (pin "7") (pinfunction "7_7") (pintype "passive"))
      (node (ref "R1029") (pin "2") (pinfunction "2_2") (pintype "passive"))
      (node (ref "R1031") (pin "2") (pinfunction "2_2") (pintype "passive"))
      (node (ref "R1032") (pin "2") (pinfunction "2_2") (pintype "passive"))
      (node (ref "R1037") (pin "2") (pinfunction "2_2") (pintype "passive"))
    )
    (net (code "35") (name "Net-(K1001-Pad2)") (class "Default")
      (node (ref "K1001") (pin "2") (pinfunction "2_2") (pintype "passive"))
      (node (ref "R1027") (pin "1") (pinfunction "1_1") (pintype "passive"))
    )
    (net (code "36") (name "Net-(K1001-Pad4)") (class "Default")
      (node (ref "K1001") (pin "4") (pinfunction "4_4") (pintype "passive"))
      (node (ref "R1026") (pin "1") (pinfunction "1_1") (pintype "passive"))
    )
    (net (code "37") (name "Net-(K1001-Pad5)") (class "Default")
      (node (ref "K1001") (pin "5") (pinfunction "5_5") (pintype "passive"))
      (node (ref "R1025") (pin "2") (pinfunction "2_2") (pintype "passive"))
      (node (ref "R1035") (pin "2") (pinfunction "2_2") (pintype "passive"))
    )
    (net (code "38") (name "Net-(Q1002-G)") (class "Default")
      (node (ref "Q1002") (pin "2") (pinfunction "G_2") (pintype "passive"))
      (node (ref "R1038") (pin "1") (pinfunction "1_1") (pintype "passive"))
    )
    (net (code "39") (name "Net-(Q1003-G)") (class "Default")
      (node (ref "Q1003") (pin "2") (pinfunction "G_2") (pintype "passive"))
      (node (ref "R1039") (pin "1") (pinfunction "1_1") (pintype "passive"))
    )
    (net (code "40") (name "Net-(Q1004-G)") (class "Default")
      (node (ref "Q1004") (pin "2") (pinfunction "G_2") (pintype "passive"))
      (node (ref "R1061") (pin "1") (pinfunction "1_1") (pintype "passive"))
    )
    (net (code "41") (name "Net-(R1025-Pad1)") (class "Default")
      (node (ref "R1025") (pin "1") (pinfunction "1_1") (pintype "passive"))
      (node (ref "R1026") (pin "2") (pinfunction "2_2") (pintype "passive"))
    )
    (net (code "42") (name "Net-(R1028-Pad2)") (class "Default")
      (node (ref "R1028") (pin "2") (pinfunction "2_2") (pintype "passive"))
      (node (ref "R1029") (pin "1") (pinfunction "1_1") (pintype "passive"))
    )
    (net (code "43") (name "Net-(R1044-Pad2)") (class "Default")
      (node (ref "R1044") (pin "2") (pinfunction "2_2") (pintype "passive"))
      (node (ref "R1045") (pin "1") (pinfunction "1_1") (pintype "passive"))
    )
    (net (code "44") (name "Net-(R1055-Pad1)") (class "Default")
      (node (ref "R1055") (pin "1") (pinfunction "1_1") (pintype "passive"))
      (node (ref "R1057") (pin "2") (pinfunction "2_2") (pintype "passive"))
      (node (ref "R1059") (pin "2") (pinfunction "2_2") (pintype "passive"))
    )
    (net (code "45") (name "Net-(U7-IN_P)") (class "Default")
      (node (ref "R33") (pin "2") (pinfunction "2_2") (pintype "passive"))
      (node (ref "U7") (pin "6") (pinfunction "IN_P_6") (pintype "passive"))
    )
    (net (code "46") (name "Net-(U1009-CLL)") (class "Default")
      (node (ref "R1054") (pin "2") (pinfunction "2_2") (pintype "passive"))
      (node (ref "U1009") (pin "14") (pinfunction "CLL_14") (pintype "passive"))
    )
    (net (code "47") (name "Net-(U1009-IN)") (class "Default")
      (node (ref "C1028") (pin "1") (pinfunction "1_1") (pintype "passive"))
      (node (ref "R1048") (pin "2") (pinfunction "2_2") (pintype "passive"))
      (node (ref "U1009") (pin "2") (pinfunction "IN_2") (pintype "passive"))
    )
    (net (code "48") (name "Net-(U1009-IN_Aux)") (class "Default")
      (node (ref "C1031") (pin "2") (pinfunction "2_2") (pintype "passive"))
      (node (ref "R1052") (pin "1") (pinfunction "1_1") (pintype "passive"))
      (node (ref "U1009") (pin "4") (pinfunction "IN_Aux_4") (pintype "passive"))
    )
    (net (code "49") (name "Net-(U1009-IN_Bias)") (class "Default")
      (node (ref "R1048") (pin "1") (pinfunction "1_1") (pintype "passive"))
      (node (ref "U1009") (pin "3") (pinfunction "IN_Bias_3") (pintype "passive"))
    )
    (net (code "50") (name "Net-(U1009-OUT)") (class "Default")
      (node (ref "R1050") (pin "2") (pinfunction "2_2") (pintype "passive"))
      (node (ref "R33") (pin "1") (pinfunction "1_1") (pintype "passive"))
      (node (ref "U1009") (pin "11") (pinfunction "OUT_11") (pintype "passive"))
    )
    (net (code "51") (name "Net-(U1009-R_Bias)") (class "Default")
      (node (ref "R1046") (pin "1") (pinfunction "1_1") (pintype "passive"))
      (node (ref "U1009") (pin "7") (pinfunction "R_Bias_7") (pintype "passive"))
    )
    (net (code "52") (name "Net-(U1010-COM)") (class "Default")
      (node (ref "C1029") (pin "2") (pinfunction "2_2") (pintype "passive"))
      (node (ref "R1056") (pin "2") (pinfunction "2_2") (pintype "passive"))
      (node (ref "U1010") (pin "1") (pinfunction "COM_1") (pintype "passive"))
      (node (ref "U1011") (pin "3") (pinfunction "+_3") (pintype "passive"))
    )
    (net (code "53") (name "Net-(U1010-NO)") (class "Default")
      (node (ref "C1029") (pin "1") (pinfunction "1_1") (pintype "passive"))
      (node (ref "R1049") (pin "1") (pinfunction "1_1") (pintype "passive"))
      (node (ref "U1010") (pin "2") (pinfunction "NO_2") (pintype "passive"))
    )
    (net (code "54") (name "Net-(U1011--)") (class "Default")
      (node (ref "C1032") (pin "2") (pinfunction "2_2") (pintype "passive"))
      (node (ref "R1050") (pin "1") (pinfunction "1_1") (pintype "passive"))
      (node (ref "R1051") (pin "2") (pinfunction "2_2") (pintype "passive"))
      (node (ref "R1055") (pin "2") (pinfunction "2_2") (pintype "passive"))
      (node (ref "U1011") (pin "2") (pinfunction "-_2") (pintype "passive"))
    )
    (net (code "55") (name "Net-(U1011-OUT)") (class "Default")
      (node (ref "C1032") (pin "1") (pinfunction "1_1") (pintype "passive"))
      (node (ref "R1052") (pin "2") (pinfunction "2_2") (pintype "passive"))
      (node (ref "U1011") (pin "6") (pinfunction "OUT_6") (pintype "passive"))
    )
    (net (code "56") (name "unconnected-(R1059-Pad1)") (class "Default")
      (node (ref "R1059") (pin "1") (pinfunction "1_1") (pintype "passive+no_connect"))
    )
    (net (code "57") (name "unconnected-(U7-AUX_N-Pad2)") (class "Default")
      (node (ref "U7") (pin "2") (pinfunction "AUX_N_2") (pintype "passive+no_connect"))
    )
    (net (code "58") (name "unconnected-(U7-AUX_P-Pad1)") (class "Default")
      (node (ref "U7") (pin "1") (pinfunction "AUX_P_1") (pintype "passive+no_connect"))
    )
    (net (code "59") (name "unconnected-(U7-AUX_VCM-Pad16)") (class "Default")
      (node (ref "U7") (pin "16") (pinfunction "AUX_VCM_16") (pintype "input+no_connect"))
    )
    (net (code "60") (name "unconnected-(U1009-NC-Pad9)") (class "Default")
      (node (ref "U1009") (pin "9") (pinfunction "NC_9") (pintype "passive+no_connect"))
    )
    (net (code "61") (name "unconnected-(U1009-NC-Pad13)") (class "Default")
      (node (ref "U1009") (pin "13") (pinfunction "NC_13") (pintype "passive+no_connect"))
    )
    (net (code "62") (name "unconnected-(U1009-NC-Pad16)") (class "Default")
      (node (ref "U1009") (pin "16") (pinfunction "NC_16") (pintype "passive+no_connect"))
    )
    (net (code "63") (name "unconnected-(U1011-N1-Pad1)") (class "Default")
      (node (ref "U1011") (pin "1") (pinfunction "N1_1") (pintype "passive+no_connect"))
    )
    (net (code "64") (name "unconnected-(U1011-N2-Pad8)") (class "Default")
      (node (ref "U1011") (pin "8") (pinfunction "N2_8") (pintype "passive+no_connect"))
    )
  )
)
